# placas_leds.net
KiCad netlist of a schematic drawn in EAGLE
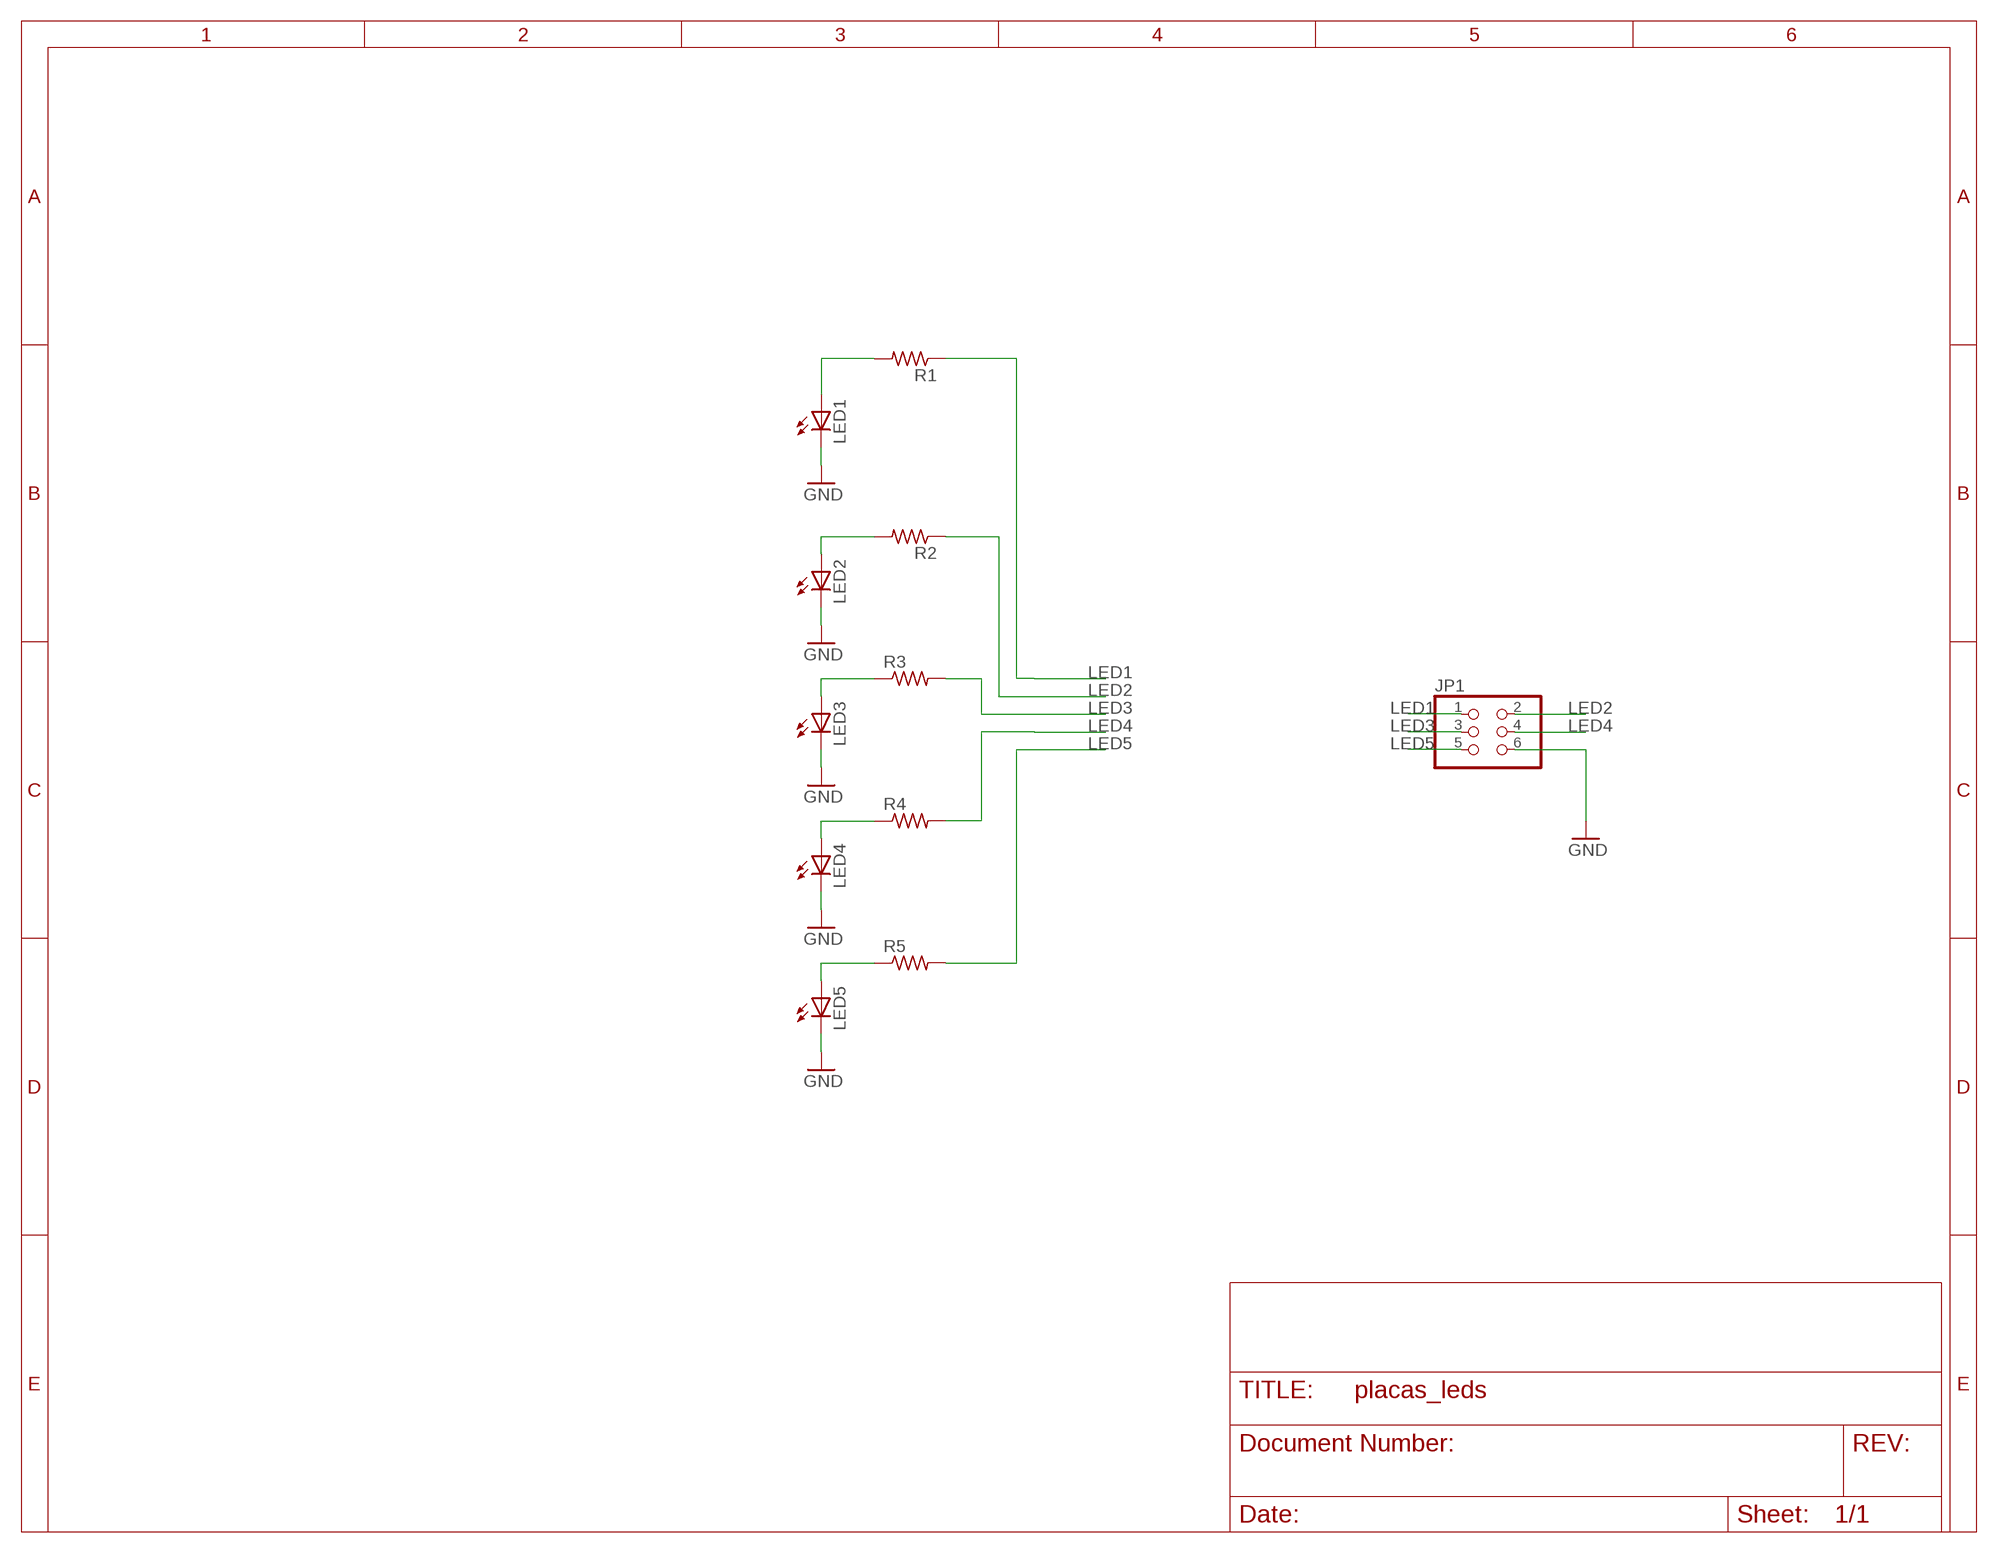
[diagram p0: schematic, sheet 1]

(export (version "E")
  (design (tool "Eeschema 10.0.6"))
  (components
    (comp (ref "JP1")
      (value "PINHD-2X3")
      (footprint "eagle-import:2X03")
      (libsource (lib "eagle-import") (part "PINHD-2X3"))
    )
    (comp (ref "LED1")
      (value "LED5MM")
      (footprint "eagle-import:LED5MM")
      (libsource (lib "eagle-import") (part "LED5MM"))
    )
    (comp (ref "LED2")
      (value "LED5MM")
      (footprint "eagle-import:LED5MM")
      (libsource (lib "eagle-import") (part "LED5MM"))
    )
    (comp (ref "LED3")
      (value "LED5MM")
      (footprint "eagle-import:LED5MM")
      (libsource (lib "eagle-import") (part "LED5MM"))
    )
    (comp (ref "LED4")
      (value "LED5MM")
      (footprint "eagle-import:LED5MM")
      (libsource (lib "eagle-import") (part "LED5MM"))
    )
    (comp (ref "LED5")
      (value "LED5MM")
      (footprint "eagle-import:LED5MM")
      (libsource (lib "eagle-import") (part "LED5MM"))
    )
    (comp (ref "R1")
      (value "R-US_0207/9")
      (footprint "eagle-import:0207_9")
      (libsource (lib "eagle-import") (part "R-US_0207/9"))
    )
    (comp (ref "R2")
      (value "R-US_0207/9")
      (footprint "eagle-import:0207_9")
      (libsource (lib "eagle-import") (part "R-US_0207/9"))
    )
    (comp (ref "R3")
      (value "R-US_0207/9")
      (footprint "eagle-import:0207_9")
      (libsource (lib "eagle-import") (part "R-US_0207/9"))
    )
    (comp (ref "R4")
      (value "R-US_0207/9")
      (footprint "eagle-import:0207_9")
      (libsource (lib "eagle-import") (part "R-US_0207/9"))
    )
    (comp (ref "R5")
      (value "R-US_0207/9")
      (footprint "eagle-import:0207_9")
      (libsource (lib "eagle-import") (part "R-US_0207/9"))
    )
  )
  (nets
    (net (code "1") (name "/LED1") (class "Default")
      (node (ref "JP1") (pin "1") (pinfunction "1_1") (pintype "passive"))
      (node (ref "R1") (pin "1") (pinfunction "1_1") (pintype "passive"))
    )
    (net (code "2") (name "/LED2") (class "Default")
      (node (ref "JP1") (pin "2") (pinfunction "2_2") (pintype "passive"))
      (node (ref "R2") (pin "1") (pinfunction "1_1") (pintype "passive"))
    )
    (net (code "3") (name "/LED3") (class "Default")
      (node (ref "JP1") (pin "3") (pinfunction "3_3") (pintype "passive"))
      (node (ref "R3") (pin "2") (pinfunction "2_2") (pintype "passive"))
    )
    (net (code "4") (name "/LED4") (class "Default")
      (node (ref "JP1") (pin "4") (pinfunction "4_4") (pintype "passive"))
      (node (ref "R4") (pin "2") (pinfunction "2_2") (pintype "passive"))
    )
    (net (code "5") (name "/LED5") (class "Default")
      (node (ref "JP1") (pin "5") (pinfunction "5_5") (pintype "passive"))
      (node (ref "R5") (pin "2") (pinfunction "2_2") (pintype "passive"))
    )
    (net (code "6") (name "GND") (class "Default")
      (node (ref "JP1") (pin "6") (pinfunction "6_6") (pintype "passive"))
      (node (ref "LED1") (pin "K") (pinfunction "C_K") (pintype "passive"))
      (node (ref "LED2") (pin "K") (pinfunction "C_K") (pintype "passive"))
      (node (ref "LED3") (pin "K") (pinfunction "C_K") (pintype "passive"))
      (node (ref "LED4") (pin "K") (pinfunction "C_K") (pintype "passive"))
      (node (ref "LED5") (pin "K") (pinfunction "C_K") (pintype "passive"))
    )
    (net (code "7") (name "Net-(LED1-PadA)") (class "Default")
      (node (ref "LED1") (pin "A") (pinfunction "A_A") (pintype "passive"))
      (node (ref "R1") (pin "2") (pinfunction "2_2") (pintype "passive"))
    )
    (net (code "8") (name "Net-(LED2-PadA)") (class "Default")
      (node (ref "LED2") (pin "A") (pinfunction "A_A") (pintype "passive"))
      (node (ref "R2") (pin "2") (pinfunction "2_2") (pintype "passive"))
    )
    (net (code "9") (name "Net-(LED3-PadA)") (class "Default")
      (node (ref "LED3") (pin "A") (pinfunction "A_A") (pintype "passive"))
      (node (ref "R3") (pin "1") (pinfunction "1_1") (pintype "passive"))
    )
    (net (code "10") (name "Net-(LED4-PadA)") (class "Default")
      (node (ref "LED4") (pin "A") (pinfunction "A_A") (pintype "passive"))
      (node (ref "R4") (pin "1") (pinfunction "1_1") (pintype "passive"))
    )
    (net (code "11") (name "Net-(LED5-PadA)") (class "Default")
      (node (ref "LED5") (pin "A") (pinfunction "A_A") (pintype "passive"))
      (node (ref "R5") (pin "1") (pinfunction "1_1") (pintype "passive"))
    )
  )
)
